# silniki.net
KiCad netlist of a schematic drawn in Altium Designer
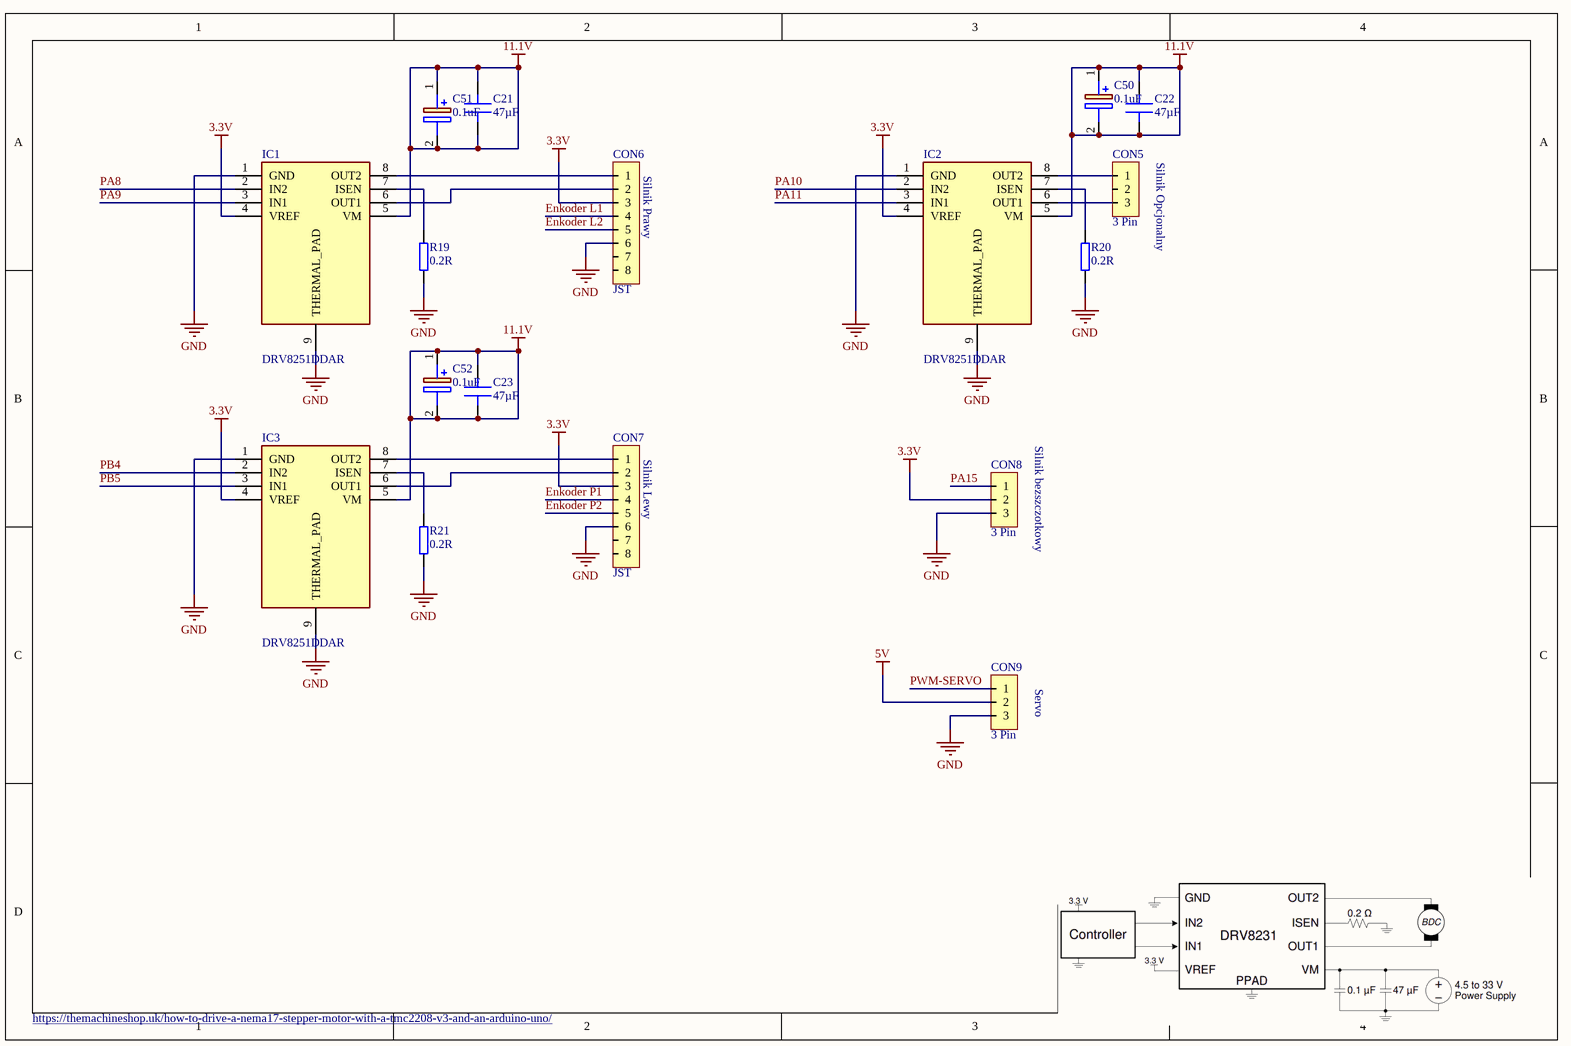
[diagram p0: silniki.SchDoc]

(export (version "E")
  (design (tool "Eeschema 10.0.6"))
  (components
    (comp (ref "C21")
      (value "47µF")
      (footprint "C 0603")
      (description "MLCC Capacitor")
      (libsource (lib "Components") (part "Capacitor"))
    )
    (comp (ref "C22")
      (value "47µF")
      (footprint "C 0603")
      (description "MLCC Capacitor")
      (libsource (lib "Components") (part "Capacitor"))
    )
    (comp (ref "C23")
      (value "47µF")
      (footprint "C 0603")
      (description "MLCC Capacitor")
      (libsource (lib "Components") (part "Capacitor"))
    )
    (comp (ref "C50")
      (value "0.1uF")
      (footprint "CAPPRD250W50D655H1250")
      (description "Capacitor Polarised")
      (fields
        (field (name "MANUFACTURER_PART_NUMBER") "UVZ1H331MPD")
        (field (name "MOUSER PART NUMBER") "647-UVZ1H331MPD")
      )
      (libsource (lib "lib-all-components") (part "UVZ1H331MPD"))
    )
    (comp (ref "C51")
      (value "0.1uF")
      (footprint "CAPPRD250W50D655H1250")
      (description "Capacitor Polarised")
      (fields
        (field (name "MANUFACTURER_PART_NUMBER") "UVZ1H331MPD")
        (field (name "MOUSER PART NUMBER") "647-UVZ1H331MPD")
      )
      (libsource (lib "lib-all-components") (part "UVZ1H331MPD"))
    )
    (comp (ref "C52")
      (value "0.1uF")
      (footprint "CAPPRD250W50D655H1250")
      (description "Capacitor Polarised")
      (fields
        (field (name "MANUFACTURER_PART_NUMBER") "UVZ1H331MPD")
        (field (name "MOUSER PART NUMBER") "647-UVZ1H331MPD")
      )
      (libsource (lib "lib-all-components") (part "UVZ1H331MPD"))
    )
    (comp (ref "CON5")
      (value "3 Pin")
      (footprint "BM03B-SRSS-TB")
      (libsource (lib "Connectors") (part "3 Pin"))
    )
    (comp (ref "CON6")
      (value "JST")
      (footprint "BM08B-SRSS-TB")
      (libsource (lib "lib-all-components") (part "8 Pin"))
    )
    (comp (ref "CON7")
      (value "JST")
      (footprint "BM08B-SRSS-TB")
      (libsource (lib "lib-all-components") (part "8 Pin"))
    )
    (comp (ref "CON8")
      (value "3 Pin")
      (footprint "BM03B-SRSS-TB")
      (libsource (lib "Connectors") (part "3 Pin"))
    )
    (comp (ref "CON9")
      (value "3 Pin")
      (footprint "BM03B-SRSS-TB")
      (libsource (lib "Connectors") (part "3 Pin"))
    )
    (comp (ref "IC1")
      (value "DRV8251DDAR")
      (footprint "SamacSys:SOIC127P600X170-9N")
      (description "Integrated Circuit")
      (fields (field (name "MOUSER PART NUMBER") "595-DRV8251DDAR"))
      (libsource (lib "Components") (part "DRV8251DDAR"))
    )
    (comp (ref "IC2")
      (value "DRV8251DDAR")
      (footprint "SamacSys:SOIC127P600X170-9N")
      (description "Integrated Circuit")
      (fields (field (name "MOUSER PART NUMBER") "595-DRV8251DDAR"))
      (libsource (lib "Components") (part "DRV8251DDAR"))
    )
    (comp (ref "IC3")
      (value "DRV8251DDAR")
      (footprint "SamacSys:SOIC127P600X170-9N")
      (description "Integrated Circuit")
      (fields (field (name "MOUSER PART NUMBER") "595-DRV8251DDAR"))
      (libsource (lib "Components") (part "DRV8251DDAR"))
    )
    (comp (ref "R19")
      (value "0.2R")
      (footprint "R 1206")
      (description "General pourpouse resistor")
      (libsource (lib "Components") (part "Resistor"))
    )
    (comp (ref "R20")
      (value "0.2R")
      (footprint "R 1206")
      (description "General pourpouse resistor")
      (libsource (lib "Components") (part "Resistor"))
    )
    (comp (ref "R21")
      (value "0.2R")
      (footprint "R 1206")
      (description "General pourpouse resistor")
      (libsource (lib "Components") (part "Resistor"))
    )
  )
  (nets
    (net (code "1") (name "/Enkoder L1") (class "Default")
      (node (ref "CON6") (pin "4") (pinfunction "4_4") (pintype "passive"))
    )
    (net (code "2") (name "/Enkoder L2") (class "Default")
      (node (ref "CON6") (pin "5") (pinfunction "5_5") (pintype "passive"))
    )
    (net (code "3") (name "/Enkoder P1") (class "Default")
      (node (ref "CON7") (pin "4") (pinfunction "4_4") (pintype "passive"))
    )
    (net (code "4") (name "/Enkoder P2") (class "Default")
      (node (ref "CON7") (pin "5") (pinfunction "5_5") (pintype "passive"))
    )
    (net (code "5") (name "/PA8") (class "Default")
      (node (ref "IC1") (pin "2") (pinfunction "IN2_2") (pintype "passive"))
    )
    (net (code "6") (name "/PA9") (class "Default")
      (node (ref "IC1") (pin "3") (pinfunction "IN1_3") (pintype "passive"))
    )
    (net (code "7") (name "/PA10") (class "Default")
      (node (ref "IC2") (pin "2") (pinfunction "IN2_2") (pintype "passive"))
    )
    (net (code "8") (name "/PA11") (class "Default")
      (node (ref "IC2") (pin "3") (pinfunction "IN1_3") (pintype "passive"))
    )
    (net (code "9") (name "/PA15") (class "Default")
      (node (ref "CON8") (pin "1") (pinfunction "1_1") (pintype "passive"))
    )
    (net (code "10") (name "/PB4") (class "Default")
      (node (ref "IC3") (pin "2") (pinfunction "IN2_2") (pintype "passive"))
    )
    (net (code "11") (name "/PB5") (class "Default")
      (node (ref "IC3") (pin "3") (pinfunction "IN1_3") (pintype "passive"))
    )
    (net (code "12") (name "/PWM-SERVO") (class "Default")
      (node (ref "CON9") (pin "1") (pinfunction "1_1") (pintype "passive"))
    )
    (net (code "13") (name "3.3V") (class "Default")
      (node (ref "CON6") (pin "3") (pinfunction "3_3") (pintype "passive"))
      (node (ref "CON7") (pin "3") (pinfunction "3_3") (pintype "passive"))
      (node (ref "CON8") (pin "2") (pinfunction "2_2") (pintype "passive"))
      (node (ref "IC1") (pin "4") (pinfunction "VREF_4") (pintype "passive"))
      (node (ref "IC2") (pin "4") (pinfunction "VREF_4") (pintype "passive"))
      (node (ref "IC3") (pin "4") (pinfunction "VREF_4") (pintype "passive"))
    )
    (net (code "14") (name "5V") (class "Default")
      (node (ref "CON9") (pin "2") (pinfunction "2_2") (pintype "passive"))
    )
    (net (code "15") (name "11.1V") (class "Default")
      (node (ref "C21") (pin "1") (pinfunction "1_1") (pintype "passive"))
      (node (ref "C21") (pin "2") (pinfunction "2_2") (pintype "passive"))
      (node (ref "C22") (pin "1") (pinfunction "1_1") (pintype "passive"))
      (node (ref "C22") (pin "2") (pinfunction "2_2") (pintype "passive"))
      (node (ref "C23") (pin "1") (pinfunction "1_1") (pintype "passive"))
      (node (ref "C23") (pin "2") (pinfunction "2_2") (pintype "passive"))
      (node (ref "C50") (pin "1") (pinfunction "+_1") (pintype "passive"))
      (node (ref "C50") (pin "2") (pinfunction "-_2") (pintype "passive"))
      (node (ref "C51") (pin "1") (pinfunction "+_1") (pintype "passive"))
      (node (ref "C51") (pin "2") (pinfunction "-_2") (pintype "passive"))
      (node (ref "C52") (pin "1") (pinfunction "+_1") (pintype "passive"))
      (node (ref "C52") (pin "2") (pinfunction "-_2") (pintype "passive"))
      (node (ref "IC1") (pin "5") (pinfunction "VM_5") (pintype "passive"))
      (node (ref "IC2") (pin "5") (pinfunction "VM_5") (pintype "passive"))
      (node (ref "IC3") (pin "5") (pinfunction "VM_5") (pintype "passive"))
    )
    (net (code "16") (name "GND") (class "Default")
      (node (ref "CON6") (pin "6") (pinfunction "6_6") (pintype "passive"))
      (node (ref "CON7") (pin "6") (pinfunction "6_6") (pintype "passive"))
      (node (ref "CON8") (pin "3") (pinfunction "3_3") (pintype "passive"))
      (node (ref "CON9") (pin "3") (pinfunction "3_3") (pintype "passive"))
      (node (ref "IC1") (pin "1") (pinfunction "GND_1") (pintype "passive"))
      (node (ref "IC1") (pin "9") (pinfunction "THERMAL_PAD_9") (pintype "passive"))
      (node (ref "IC2") (pin "1") (pinfunction "GND_1") (pintype "passive"))
      (node (ref "IC2") (pin "9") (pinfunction "THERMAL_PAD_9") (pintype "passive"))
      (node (ref "IC3") (pin "1") (pinfunction "GND_1") (pintype "passive"))
      (node (ref "IC3") (pin "9") (pinfunction "THERMAL_PAD_9") (pintype "passive"))
      (node (ref "R19") (pin "1") (pinfunction "1_1") (pintype "passive"))
      (node (ref "R20") (pin "1") (pinfunction "1_1") (pintype "passive"))
      (node (ref "R21") (pin "1") (pinfunction "1_1") (pintype "passive"))
    )
    (net (code "17") (name "Net-(IC1-ISEN)") (class "Default")
      (node (ref "IC1") (pin "7") (pinfunction "ISEN_7") (pintype "passive"))
      (node (ref "R19") (pin "2") (pinfunction "2_2") (pintype "passive"))
    )
    (net (code "18") (name "Net-(IC1-OUT1)") (class "Default")
      (node (ref "CON6") (pin "2") (pinfunction "2_2") (pintype "passive"))
      (node (ref "IC1") (pin "6") (pinfunction "OUT1_6") (pintype "passive"))
    )
    (net (code "19") (name "Net-(IC1-OUT2)") (class "Default")
      (node (ref "CON6") (pin "1") (pinfunction "1_1") (pintype "passive"))
      (node (ref "IC1") (pin "8") (pinfunction "OUT2_8") (pintype "passive"))
    )
    (net (code "20") (name "Net-(IC2-ISEN)") (class "Default")
      (node (ref "IC2") (pin "7") (pinfunction "ISEN_7") (pintype "passive"))
      (node (ref "R20") (pin "2") (pinfunction "2_2") (pintype "passive"))
    )
    (net (code "21") (name "Net-(IC2-OUT1)") (class "Default")
      (node (ref "CON5") (pin "3") (pinfunction "3_3") (pintype "passive"))
      (node (ref "IC2") (pin "6") (pinfunction "OUT1_6") (pintype "passive"))
    )
    (net (code "22") (name "Net-(IC2-OUT2)") (class "Default")
      (node (ref "CON5") (pin "1") (pinfunction "1_1") (pintype "passive"))
      (node (ref "IC2") (pin "8") (pinfunction "OUT2_8") (pintype "passive"))
    )
    (net (code "23") (name "Net-(IC3-ISEN)") (class "Default")
      (node (ref "IC3") (pin "7") (pinfunction "ISEN_7") (pintype "passive"))
      (node (ref "R21") (pin "2") (pinfunction "2_2") (pintype "passive"))
    )
    (net (code "24") (name "Net-(IC3-OUT1)") (class "Default")
      (node (ref "CON7") (pin "2") (pinfunction "2_2") (pintype "passive"))
      (node (ref "IC3") (pin "6") (pinfunction "OUT1_6") (pintype "passive"))
    )
    (net (code "25") (name "Net-(IC3-OUT2)") (class "Default")
      (node (ref "CON7") (pin "1") (pinfunction "1_1") (pintype "passive"))
      (node (ref "IC3") (pin "8") (pinfunction "OUT2_8") (pintype "passive"))
    )
    (net (code "26") (name "unconnected-(CON5-Pad2)") (class "Default")
      (node (ref "CON5") (pin "2") (pinfunction "2_2") (pintype "passive"))
    )
    (net (code "27") (name "unconnected-(CON6-Pad7)") (class "Default")
      (node (ref "CON6") (pin "7") (pinfunction "7_7") (pintype "passive"))
    )
    (net (code "28") (name "unconnected-(CON6-Pad8)") (class "Default")
      (node (ref "CON6") (pin "8") (pinfunction "8_8") (pintype "passive"))
    )
    (net (code "29") (name "unconnected-(CON7-Pad7)") (class "Default")
      (node (ref "CON7") (pin "7") (pinfunction "7_7") (pintype "passive"))
    )
    (net (code "30") (name "unconnected-(CON7-Pad8)") (class "Default")
      (node (ref "CON7") (pin "8") (pinfunction "8_8") (pintype "passive"))
    )
  )
)
